# DW_RTK_PCB_Schematic_EasyEDA.net
KiCad netlist of a schematic drawn in EasyEDA
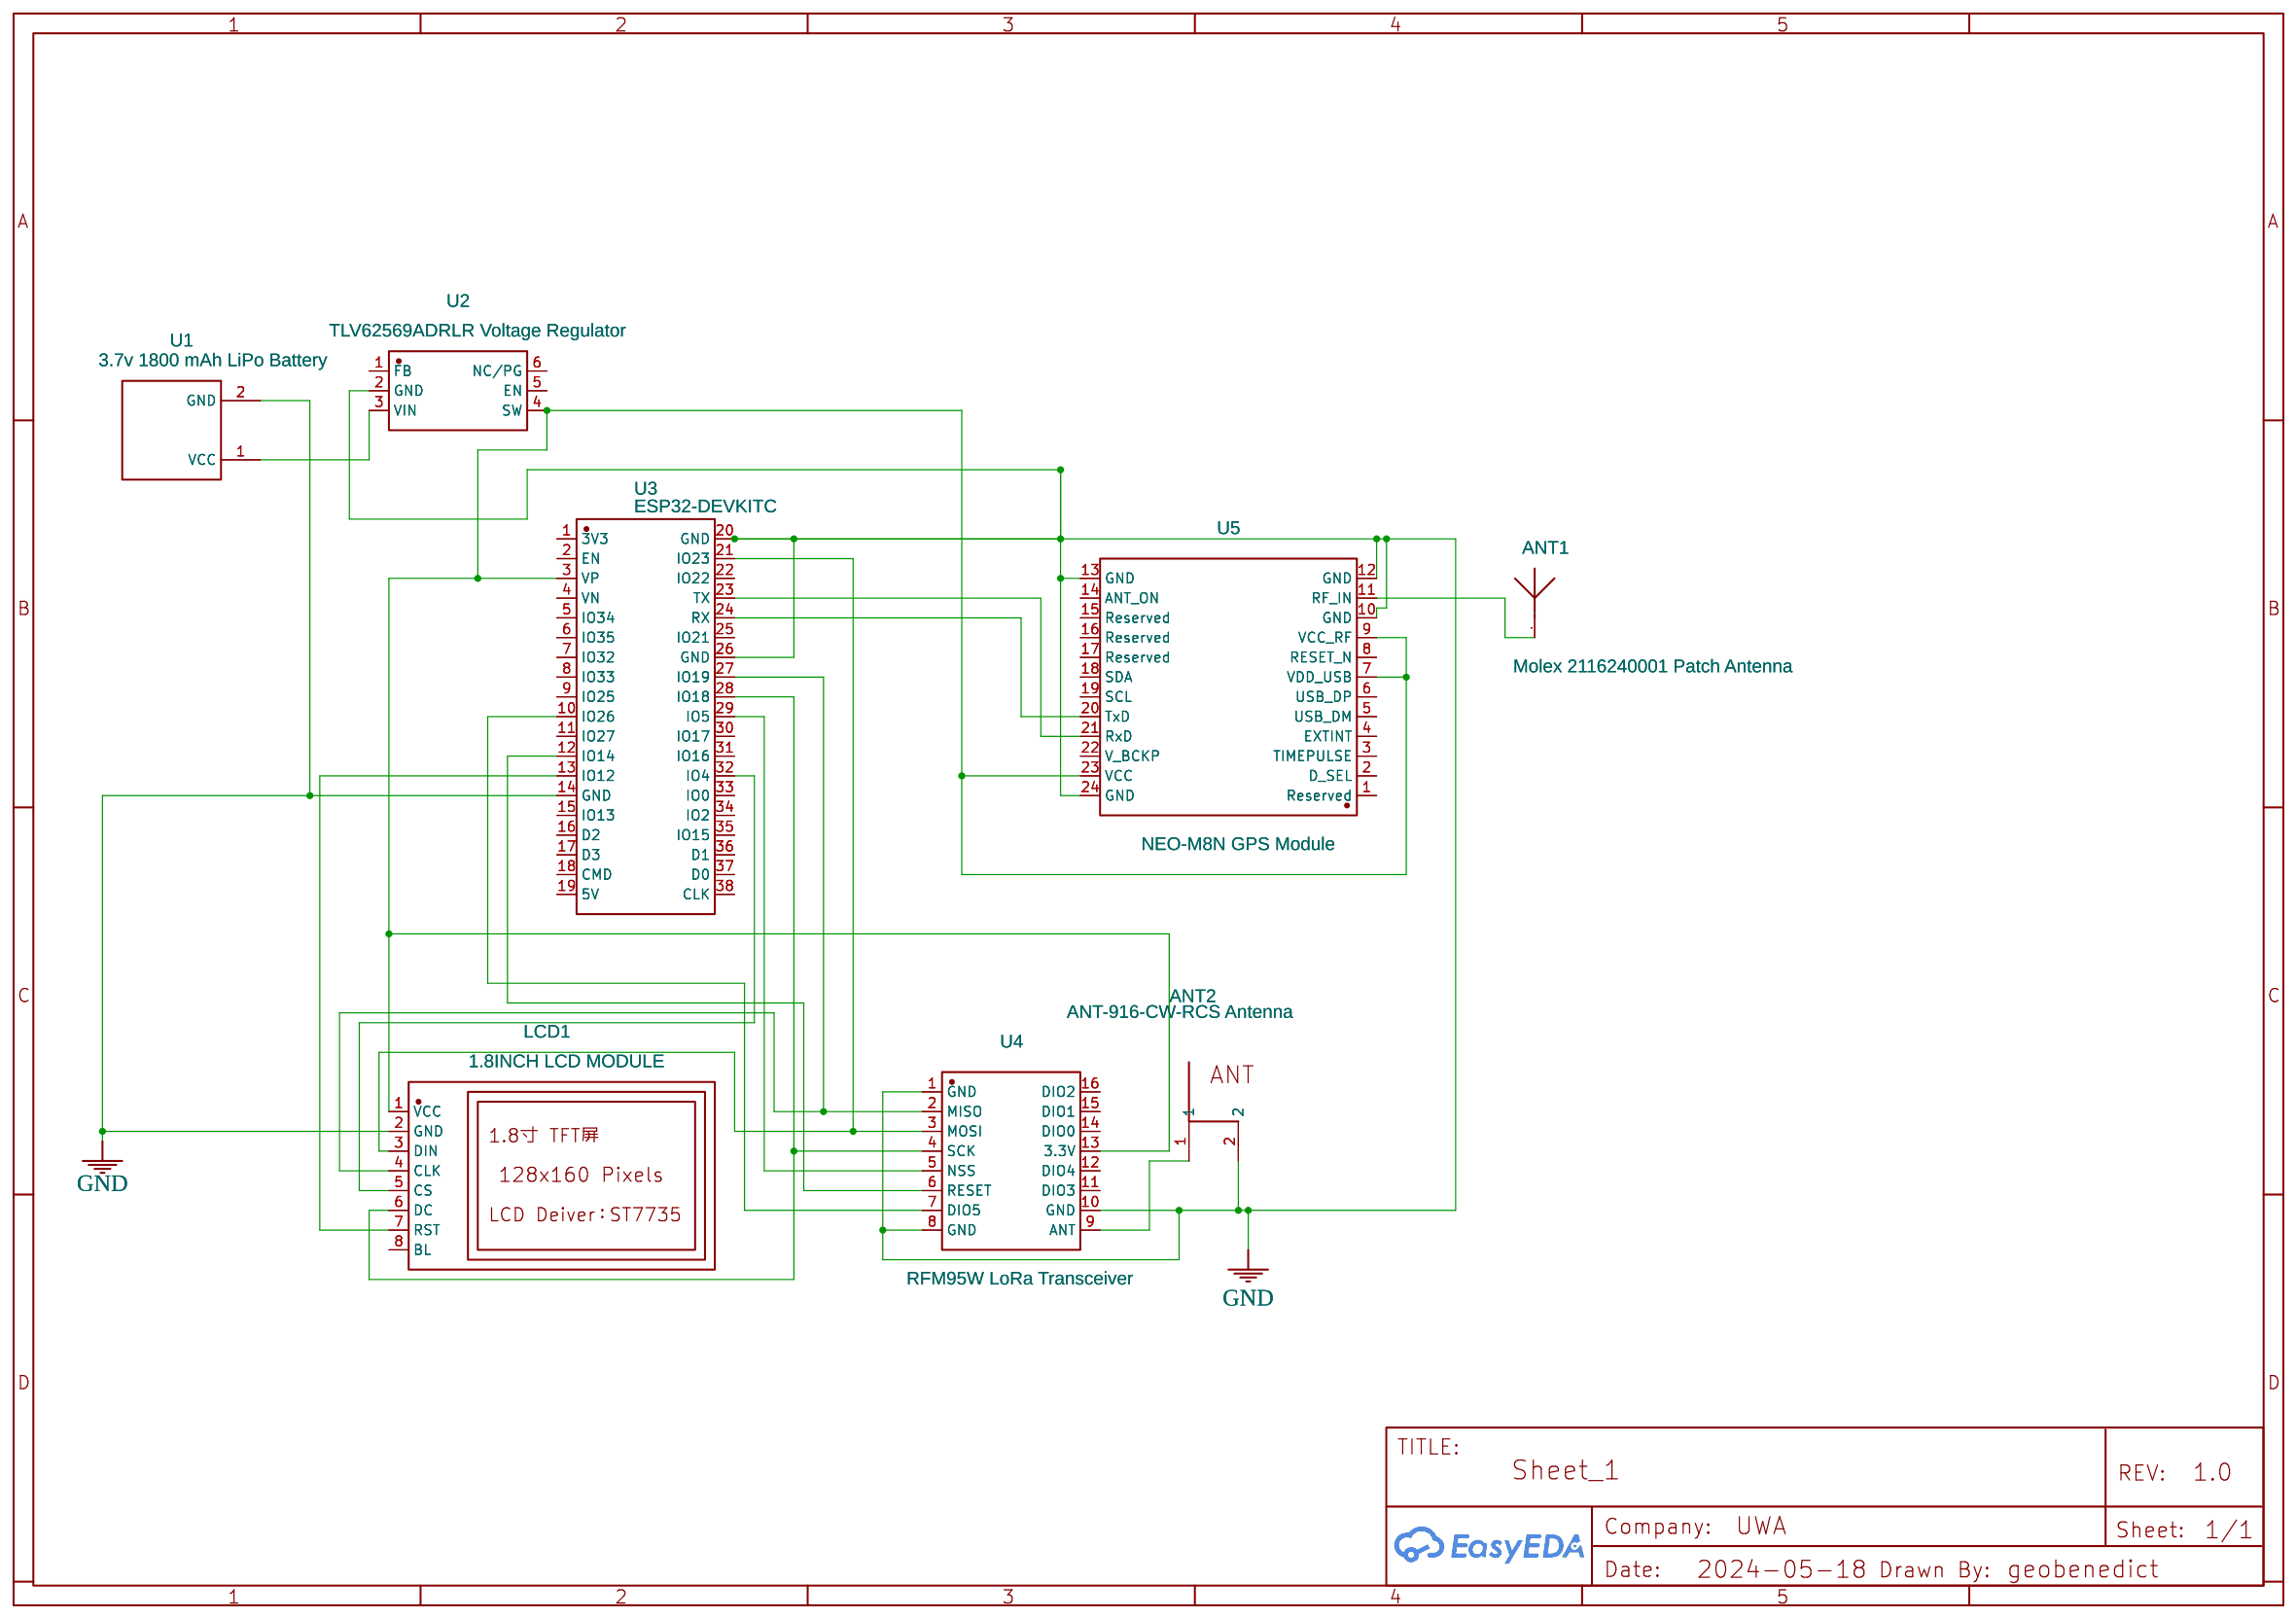
[diagram p0: schematic sheet]

(export (version "E")
  (design (tool "Eeschema 10.0.6"))
  (components
    (comp (ref "ANT1")
      (value "Molex 2116240001 Patch Antenna")
      (fields (field (name "Manufacturer Part") "YG0005AA") (field (name "Manufacturer") "Quectel(移远)"))
      (libsource (lib "") (part "YG0005AA"))
    )
    (comp (ref "ANT2")
      (value "ANT-916-CW-RCS Antenna")
      (fields (field (name "Manufacturer") "Linx"))
      (libsource (lib "") (part "LINX ANTENNA USP410"))
    )
    (comp (ref "LCD1")
      (value "1.8INCH LCD MODULE")
      (fields
        (field (name "Manufacturer Part") "1.8inch LCD Module")
        (field (name "Manufacturer") "Waveshare(微雪电子)")
      )
      (libsource (lib "") (part "1.8INCH LCD MODULE"))
    )
    (comp (ref "U1") (value "3.7v 1800 mAh LiPo Battery") (libsource (lib "") (part "3.7v 1800 mAh LiPo")))
    (comp (ref "U2")
      (value "TLV62569ADRLR Voltage Regulator")
      (fields (field (name "Manufacturer Part") "TLV62569ADRLR") (field (name "Manufacturer") "TI(德州仪器)"))
      (libsource (lib "") (part "TLV62569ADRLR"))
    )
    (comp (ref "U3")
      (value "ESP32-DEVKITC")
      (fields
        (field (name "Manufacturer Part") "ESP32-DevKitC")
        (field (name "Manufacturer") "ESPRESSIF(乐鑫)")
      )
      (libsource (lib "") (part "ESP32-DEVKITC"))
    )
    (comp (ref "U4")
      (value "RFM95W LoRa Transceiver")
      (fields (field (name "Manufacturer Part") "RFM95W"))
      (libsource (lib "") (part "RFM95W"))
    )
    (comp (ref "U5")
      (value "NEO-M8N GPS Module")
      (fields (field (name "Manufacturer Part") "NEO-M8N"))
      (libsource (lib "") (part "NEO-M8N"))
    )
  )
  (nets
    (net (code "1") (name "GND") (class "Default")
      (node (ref "ANT2") (pin "2") (pinfunction "2_2") (pintype "unspecified"))
      (node (ref "LCD1") (pin "2") (pinfunction "GND_2") (pintype "unspecified"))
      (node (ref "U1") (pin "2") (pinfunction "GND_2") (pintype "unspecified"))
      (node (ref "U2") (pin "2") (pinfunction "GND_2") (pintype "unspecified"))
      (node (ref "U3") (pin "14") (pinfunction "GND_14") (pintype "unspecified"))
      (node (ref "U3") (pin "20") (pinfunction "GND_20") (pintype "unspecified"))
      (node (ref "U3") (pin "26") (pinfunction "GND_26") (pintype "unspecified"))
      (node (ref "U4") (pin "1") (pinfunction "GND_1") (pintype "unspecified"))
      (node (ref "U4") (pin "10") (pinfunction "GND_10") (pintype "unspecified"))
      (node (ref "U4") (pin "8") (pinfunction "GND_8") (pintype "unspecified"))
      (node (ref "U5") (pin "10") (pinfunction "GND_10") (pintype "unspecified"))
      (node (ref "U5") (pin "12") (pinfunction "GND_12") (pintype "unspecified"))
      (node (ref "U5") (pin "13") (pinfunction "GND_13") (pintype "unspecified"))
      (node (ref "U5") (pin "24") (pinfunction "GND_24") (pintype "unspecified"))
    )
    (net (code "2") (name "Net-(LCD1-CLK)") (class "Default")
      (node (ref "LCD1") (pin "4") (pinfunction "CLK_4") (pintype "unspecified"))
      (node (ref "U3") (pin "27") (pinfunction "IO19_27") (pintype "unspecified"))
      (node (ref "U4") (pin "2") (pinfunction "MISO_2") (pintype "unspecified"))
    )
    (net (code "3") (name "Net-(LCD1-CS)") (class "Default")
      (node (ref "LCD1") (pin "5") (pinfunction "CS_5") (pintype "unspecified"))
      (node (ref "U3") (pin "32") (pinfunction "IO4_32") (pintype "unspecified"))
    )
    (net (code "4") (name "Net-(LCD1-DC)") (class "Default")
      (node (ref "LCD1") (pin "6") (pinfunction "DC_6") (pintype "unspecified"))
      (node (ref "U3") (pin "28") (pinfunction "IO18_28") (pintype "unspecified"))
      (node (ref "U4") (pin "4") (pinfunction "SCK_4") (pintype "unspecified"))
    )
    (net (code "5") (name "Net-(LCD1-DIN)") (class "Default")
      (node (ref "LCD1") (pin "3") (pinfunction "DIN_3") (pintype "unspecified"))
      (node (ref "U3") (pin "21") (pinfunction "IO23_21") (pintype "unspecified"))
      (node (ref "U4") (pin "3") (pinfunction "MOSI_3") (pintype "unspecified"))
    )
    (net (code "6") (name "Net-(LCD1-RST)") (class "Default")
      (node (ref "LCD1") (pin "7") (pinfunction "RST_7") (pintype "unspecified"))
      (node (ref "U3") (pin "13") (pinfunction "IO12_13") (pintype "unspecified"))
    )
    (net (code "7") (name "Net-(LCD1-VCC)") (class "Default")
      (node (ref "LCD1") (pin "1") (pinfunction "VCC_1") (pintype "unspecified"))
      (node (ref "U2") (pin "4") (pinfunction "SW_4") (pintype "unspecified"))
      (node (ref "U3") (pin "3") (pinfunction "VP_3") (pintype "unspecified"))
      (node (ref "U4") (pin "13") (pinfunction "3.3V_13") (pintype "unspecified"))
      (node (ref "U5") (pin "23") (pinfunction "VCC_23") (pintype "unspecified"))
      (node (ref "U5") (pin "7") (pinfunction "VDD_USB_7") (pintype "unspecified"))
      (node (ref "U5") (pin "9") (pinfunction "VCC_RF_9") (pintype "unspecified"))
    )
    (net (code "8") (name "Net-(U1-VCC)") (class "Default")
      (node (ref "U1") (pin "1") (pinfunction "VCC_1") (pintype "unspecified"))
      (node (ref "U2") (pin "3") (pinfunction "VIN_3") (pintype "unspecified"))
    )
    (net (code "9") (name "Net-(U3-IO5)") (class "Default")
      (node (ref "U3") (pin "29") (pinfunction "IO5_29") (pintype "unspecified"))
      (node (ref "U4") (pin "5") (pinfunction "NSS_5") (pintype "unspecified"))
    )
    (net (code "10") (name "Net-(U3-IO14)") (class "Default")
      (node (ref "U3") (pin "12") (pinfunction "IO14_12") (pintype "unspecified"))
      (node (ref "U4") (pin "6") (pinfunction "RESET_6") (pintype "unspecified"))
    )
    (net (code "11") (name "Net-(U3-IO26)") (class "Default")
      (node (ref "U3") (pin "10") (pinfunction "IO26_10") (pintype "unspecified"))
      (node (ref "U4") (pin "7") (pinfunction "DIO5_7") (pintype "unspecified"))
    )
    (net (code "12") (name "Net-(U3-RX)") (class "Default")
      (node (ref "U3") (pin "24") (pinfunction "RX_24") (pintype "unspecified"))
      (node (ref "U5") (pin "20") (pinfunction "TxD_20") (pintype "unspecified"))
    )
    (net (code "13") (name "Net-(U3-TX)") (class "Default")
      (node (ref "U3") (pin "23") (pinfunction "TX_23") (pintype "unspecified"))
      (node (ref "U5") (pin "21") (pinfunction "RxD_21") (pintype "unspecified"))
    )
    (net (code "14") (name "Net-(U4-ANT)") (class "Default")
      (node (ref "ANT2") (pin "1") (pinfunction "1_1") (pintype "unspecified"))
      (node (ref "U4") (pin "9") (pinfunction "ANT_9") (pintype "unspecified"))
    )
    (net (code "15") (name "Net-(U5-RF_IN)") (class "Default")
      (node (ref "ANT1") (pin "1") (pinfunction "1_1") (pintype "unspecified"))
      (node (ref "U5") (pin "11") (pinfunction "RF_IN_11") (pintype "unspecified"))
    )
    (net (code "16") (name "unconnected-(LCD1-BL-Pad8)") (class "Default")
      (node (ref "LCD1") (pin "8") (pinfunction "BL_8") (pintype "unspecified"))
    )
    (net (code "17") (name "unconnected-(U2-EN-Pad5)") (class "Default")
      (node (ref "U2") (pin "5") (pinfunction "EN_5") (pintype "unspecified"))
    )
    (net (code "18") (name "unconnected-(U2-FB-Pad1)") (class "Default")
      (node (ref "U2") (pin "1") (pinfunction "FB_1") (pintype "unspecified"))
    )
    (net (code "19") (name "unconnected-(U2-NC{slash}PG-Pad6)") (class "Default")
      (node (ref "U2") (pin "6") (pinfunction "NC/PG_6") (pintype "unspecified"))
    )
    (net (code "20") (name "unconnected-(U3-3V3-Pad1)") (class "Default")
      (node (ref "U3") (pin "1") (pinfunction "3V3_1") (pintype "unspecified"))
    )
    (net (code "21") (name "unconnected-(U3-5V-Pad19)") (class "Default")
      (node (ref "U3") (pin "19") (pinfunction "5V_19") (pintype "unspecified"))
    )
    (net (code "22") (name "unconnected-(U3-CLK-Pad38)") (class "Default")
      (node (ref "U3") (pin "38") (pinfunction "CLK_38") (pintype "unspecified"))
    )
    (net (code "23") (name "unconnected-(U3-CMD-Pad18)") (class "Default")
      (node (ref "U3") (pin "18") (pinfunction "CMD_18") (pintype "unspecified"))
    )
    (net (code "24") (name "unconnected-(U3-D0-Pad37)") (class "Default")
      (node (ref "U3") (pin "37") (pinfunction "D0_37") (pintype "unspecified"))
    )
    (net (code "25") (name "unconnected-(U3-D1-Pad36)") (class "Default")
      (node (ref "U3") (pin "36") (pinfunction "D1_36") (pintype "unspecified"))
    )
    (net (code "26") (name "unconnected-(U3-D2-Pad16)") (class "Default")
      (node (ref "U3") (pin "16") (pinfunction "D2_16") (pintype "unspecified"))
    )
    (net (code "27") (name "unconnected-(U3-D3-Pad17)") (class "Default")
      (node (ref "U3") (pin "17") (pinfunction "D3_17") (pintype "unspecified"))
    )
    (net (code "28") (name "unconnected-(U3-EN-Pad2)") (class "Default")
      (node (ref "U3") (pin "2") (pinfunction "EN_2") (pintype "unspecified"))
    )
    (net (code "29") (name "unconnected-(U3-IO0-Pad33)") (class "Default")
      (node (ref "U3") (pin "33") (pinfunction "IO0_33") (pintype "unspecified"))
    )
    (net (code "30") (name "unconnected-(U3-IO2-Pad34)") (class "Default")
      (node (ref "U3") (pin "34") (pinfunction "IO2_34") (pintype "unspecified"))
    )
    (net (code "31") (name "unconnected-(U3-IO13-Pad15)") (class "Default")
      (node (ref "U3") (pin "15") (pinfunction "IO13_15") (pintype "unspecified"))
    )
    (net (code "32") (name "unconnected-(U3-IO15-Pad35)") (class "Default")
      (node (ref "U3") (pin "35") (pinfunction "IO15_35") (pintype "unspecified"))
    )
    (net (code "33") (name "unconnected-(U3-IO16-Pad31)") (class "Default")
      (node (ref "U3") (pin "31") (pinfunction "IO16_31") (pintype "unspecified"))
    )
    (net (code "34") (name "unconnected-(U3-IO17-Pad30)") (class "Default")
      (node (ref "U3") (pin "30") (pinfunction "IO17_30") (pintype "unspecified"))
    )
    (net (code "35") (name "unconnected-(U3-IO21-Pad25)") (class "Default")
      (node (ref "U3") (pin "25") (pinfunction "IO21_25") (pintype "unspecified"))
    )
    (net (code "36") (name "unconnected-(U3-IO22-Pad22)") (class "Default")
      (node (ref "U3") (pin "22") (pinfunction "IO22_22") (pintype "unspecified"))
    )
    (net (code "37") (name "unconnected-(U3-IO25-Pad9)") (class "Default")
      (node (ref "U3") (pin "9") (pinfunction "IO25_9") (pintype "unspecified"))
    )
    (net (code "38") (name "unconnected-(U3-IO27-Pad11)") (class "Default")
      (node (ref "U3") (pin "11") (pinfunction "IO27_11") (pintype "unspecified"))
    )
    (net (code "39") (name "unconnected-(U3-IO32-Pad7)") (class "Default")
      (node (ref "U3") (pin "7") (pinfunction "IO32_7") (pintype "unspecified"))
    )
    (net (code "40") (name "unconnected-(U3-IO33-Pad8)") (class "Default")
      (node (ref "U3") (pin "8") (pinfunction "IO33_8") (pintype "unspecified"))
    )
    (net (code "41") (name "unconnected-(U3-IO34-Pad5)") (class "Default")
      (node (ref "U3") (pin "5") (pinfunction "IO34_5") (pintype "unspecified"))
    )
    (net (code "42") (name "unconnected-(U3-IO35-Pad6)") (class "Default")
      (node (ref "U3") (pin "6") (pinfunction "IO35_6") (pintype "unspecified"))
    )
    (net (code "43") (name "unconnected-(U3-VN-Pad4)") (class "Default")
      (node (ref "U3") (pin "4") (pinfunction "VN_4") (pintype "unspecified"))
    )
    (net (code "44") (name "unconnected-(U4-DIO0-Pad14)") (class "Default")
      (node (ref "U4") (pin "14") (pinfunction "DIO0_14") (pintype "unspecified"))
    )
    (net (code "45") (name "unconnected-(U4-DIO1-Pad15)") (class "Default")
      (node (ref "U4") (pin "15") (pinfunction "DIO1_15") (pintype "unspecified"))
    )
    (net (code "46") (name "unconnected-(U4-DIO2-Pad16)") (class "Default")
      (node (ref "U4") (pin "16") (pinfunction "DIO2_16") (pintype "unspecified"))
    )
    (net (code "47") (name "unconnected-(U4-DIO3-Pad11)") (class "Default")
      (node (ref "U4") (pin "11") (pinfunction "DIO3_11") (pintype "unspecified"))
    )
    (net (code "48") (name "unconnected-(U4-DIO4-Pad12)") (class "Default")
      (node (ref "U4") (pin "12") (pinfunction "DIO4_12") (pintype "unspecified"))
    )
    (net (code "49") (name "unconnected-(U5-ANT_ON-Pad14)") (class "Default")
      (node (ref "U5") (pin "14") (pinfunction "ANT_ON_14") (pintype "unspecified"))
    )
    (net (code "50") (name "unconnected-(U5-D_SEL-Pad2)") (class "Default")
      (node (ref "U5") (pin "2") (pinfunction "D_SEL_2") (pintype "unspecified"))
    )
    (net (code "51") (name "unconnected-(U5-EXTINT-Pad4)") (class "Default")
      (node (ref "U5") (pin "4") (pinfunction "EXTINT_4") (pintype "unspecified"))
    )
    (net (code "52") (name "unconnected-(U5-RESET_N-Pad8)") (class "Default")
      (node (ref "U5") (pin "8") (pinfunction "RESET_N_8") (pintype "unspecified"))
    )
    (net (code "53") (name "unconnected-(U5-Reserved-Pad1)") (class "Default")
      (node (ref "U5") (pin "1") (pinfunction "Reserved_1") (pintype "unspecified"))
    )
    (net (code "54") (name "unconnected-(U5-Reserved-Pad15)") (class "Default")
      (node (ref "U5") (pin "15") (pinfunction "Reserved_15") (pintype "unspecified"))
    )
    (net (code "55") (name "unconnected-(U5-Reserved-Pad16)") (class "Default")
      (node (ref "U5") (pin "16") (pinfunction "Reserved_16") (pintype "unspecified"))
    )
    (net (code "56") (name "unconnected-(U5-Reserved-Pad17)") (class "Default")
      (node (ref "U5") (pin "17") (pinfunction "Reserved_17") (pintype "unspecified"))
    )
    (net (code "57") (name "unconnected-(U5-SCL-Pad19)") (class "Default")
      (node (ref "U5") (pin "19") (pinfunction "SCL_19") (pintype "unspecified"))
    )
    (net (code "58") (name "unconnected-(U5-SDA-Pad18)") (class "Default")
      (node (ref "U5") (pin "18") (pinfunction "SDA_18") (pintype "unspecified"))
    )
    (net (code "59") (name "unconnected-(U5-TIMEPULSE-Pad3)") (class "Default")
      (node (ref "U5") (pin "3") (pinfunction "TIMEPULSE_3") (pintype "unspecified"))
    )
    (net (code "60") (name "unconnected-(U5-USB_DM-Pad5)") (class "Default")
      (node (ref "U5") (pin "5") (pinfunction "USB_DM_5") (pintype "unspecified"))
    )
    (net (code "61") (name "unconnected-(U5-USB_DP-Pad6)") (class "Default")
      (node (ref "U5") (pin "6") (pinfunction "USB_DP_6") (pintype "unspecified"))
    )
    (net (code "62") (name "unconnected-(U5-V_BCKP-Pad22)") (class "Default")
      (node (ref "U5") (pin "22") (pinfunction "V_BCKP_22") (pintype "unspecified"))
    )
  )
)
